# QCopterMV_LCD_Sch.net
KiCad netlist of a schematic drawn in Altium Designer
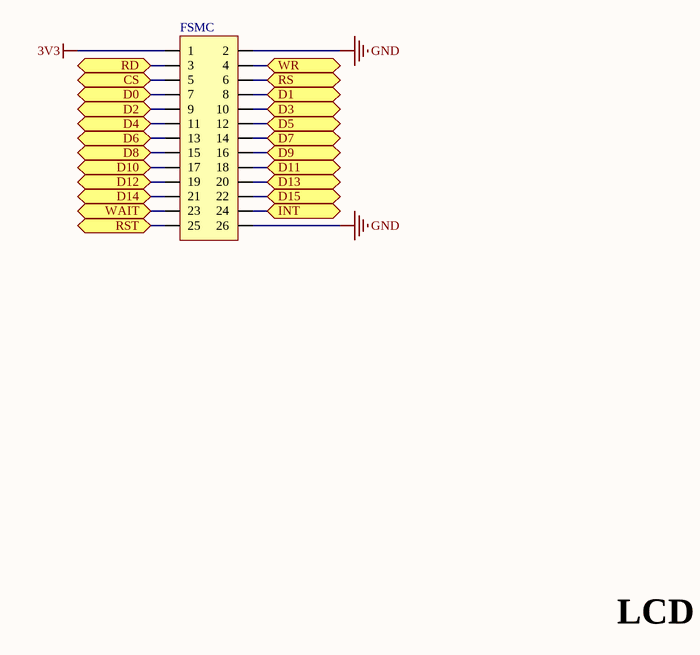
[diagram p0: QCopterMV_LCD_Sch.SchDoc]

(export (version "E")
  (design (tool "Eeschema 10.0.6"))
  (components
    (comp (ref "FSMC")
      (value "HDR2X13_180FTB_2.54")
      (footprint "PCB_Connector:HDR2X13_180FTB_2.54")
      (description "Header")
      (libsource (lib "SCH_Connector") (part "HDR2X13_180FTB_2.54"))
    )
  )
  (nets
    (net (code "1") (name "/CS") (class "Default")
      (node (ref "FSMC") (pin "5") (pinfunction "5_5") (pintype "passive"))
    )
    (net (code "2") (name "/D0") (class "Default")
      (node (ref "FSMC") (pin "7") (pinfunction "7_7") (pintype "passive"))
    )
    (net (code "3") (name "/D1") (class "Default")
      (node (ref "FSMC") (pin "8") (pinfunction "8_8") (pintype "passive"))
    )
    (net (code "4") (name "/D2") (class "Default")
      (node (ref "FSMC") (pin "9") (pinfunction "9_9") (pintype "passive"))
    )
    (net (code "5") (name "/D3") (class "Default")
      (node (ref "FSMC") (pin "10") (pinfunction "10_10") (pintype "passive"))
    )
    (net (code "6") (name "/D4") (class "Default")
      (node (ref "FSMC") (pin "11") (pinfunction "11_11") (pintype "passive"))
    )
    (net (code "7") (name "/D5") (class "Default")
      (node (ref "FSMC") (pin "12") (pinfunction "12_12") (pintype "passive"))
    )
    (net (code "8") (name "/D6") (class "Default")
      (node (ref "FSMC") (pin "13") (pinfunction "13_13") (pintype "passive"))
    )
    (net (code "9") (name "/D7") (class "Default")
      (node (ref "FSMC") (pin "14") (pinfunction "14_14") (pintype "passive"))
    )
    (net (code "10") (name "/D8") (class "Default")
      (node (ref "FSMC") (pin "15") (pinfunction "15_15") (pintype "passive"))
    )
    (net (code "11") (name "/D9") (class "Default")
      (node (ref "FSMC") (pin "16") (pinfunction "16_16") (pintype "passive"))
    )
    (net (code "12") (name "/D10") (class "Default")
      (node (ref "FSMC") (pin "17") (pinfunction "17_17") (pintype "passive"))
    )
    (net (code "13") (name "/D11") (class "Default")
      (node (ref "FSMC") (pin "18") (pinfunction "18_18") (pintype "passive"))
    )
    (net (code "14") (name "/D12") (class "Default")
      (node (ref "FSMC") (pin "19") (pinfunction "19_19") (pintype "passive"))
    )
    (net (code "15") (name "/D13") (class "Default")
      (node (ref "FSMC") (pin "20") (pinfunction "20_20") (pintype "passive"))
    )
    (net (code "16") (name "/D14") (class "Default")
      (node (ref "FSMC") (pin "21") (pinfunction "21_21") (pintype "passive"))
    )
    (net (code "17") (name "/D15") (class "Default")
      (node (ref "FSMC") (pin "22") (pinfunction "22_22") (pintype "passive"))
    )
    (net (code "18") (name "/INT") (class "Default")
      (node (ref "FSMC") (pin "24") (pinfunction "24_24") (pintype "passive"))
    )
    (net (code "19") (name "/RD") (class "Default")
      (node (ref "FSMC") (pin "3") (pinfunction "3_3") (pintype "passive"))
    )
    (net (code "20") (name "/RS") (class "Default")
      (node (ref "FSMC") (pin "6") (pinfunction "6_6") (pintype "passive"))
    )
    (net (code "21") (name "/RST") (class "Default")
      (node (ref "FSMC") (pin "25") (pinfunction "25_25") (pintype "passive"))
    )
    (net (code "22") (name "/WAIT") (class "Default")
      (node (ref "FSMC") (pin "23") (pinfunction "23_23") (pintype "passive"))
    )
    (net (code "23") (name "/WR") (class "Default")
      (node (ref "FSMC") (pin "4") (pinfunction "4_4") (pintype "passive"))
    )
    (net (code "24") (name "3V3") (class "Default")
      (node (ref "FSMC") (pin "1") (pinfunction "1_1") (pintype "passive"))
    )
    (net (code "25") (name "GND") (class "Default")
      (node (ref "FSMC") (pin "2") (pinfunction "2_2") (pintype "passive"))
      (node (ref "FSMC") (pin "26") (pinfunction "26_26") (pintype "passive"))
    )
  )
)
